# ConnectBox_Charger.net
KiCad netlist of a schematic drawn in EAGLE
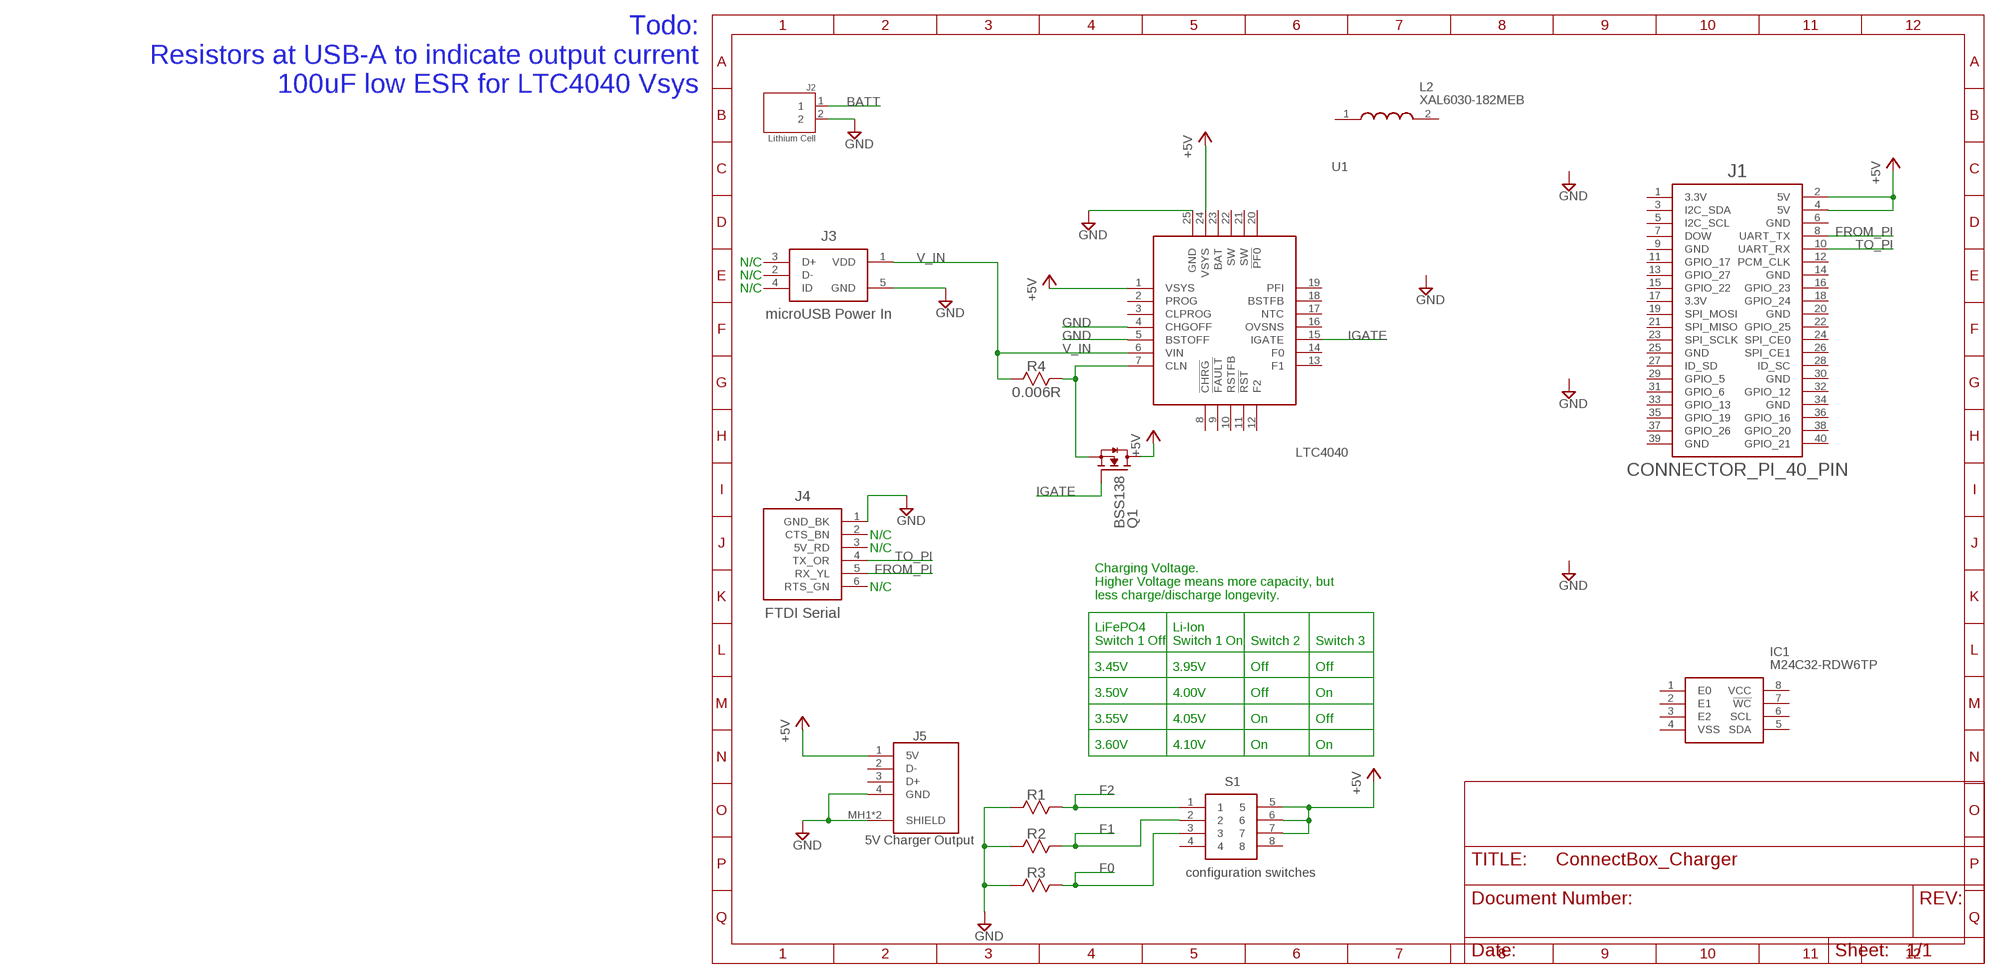
[diagram p0: schematic, sheet 1]

(export (version "E")
  (design (tool "Eeschema 10.0.6"))
  (components
    (comp (ref "IC1")
      (value "M24C32-RDW6TP")
      (footprint "eagle-import:SOP65P640X120-8N")
      (fields (field (name "MOUSER_PART_NUMBER") "511-M24C32-RDW6TP"))
      (libsource (lib "eagle-import") (part "M24C32-RDW6TP"))
    )
    (comp (ref "J1")
      (value "CONNECTOR_PI_40_PIN")
      (footprint "eagle-import:2X20")
      (libsource (lib "eagle-import") (part "CONNECTOR_PI_40_PIN"))
    )
    (comp (ref "J2")
      (value "Lithium Cell")
      (footprint "eagle-import:JST_S2B-PH-SM4-TB(LF)(SN)")
      (fields (field (name "MF") "JST Sales") (field (name "MP") "S2B-PH-SM4-TB_LF__SN_"))
      (libsource (lib "eagle-import") (part "S2B-PH-SM4-TB(LF)(SN)"))
    )
    (comp (ref "J3")
      (value "microUSB Power In")
      (footprint "eagle-import:FRAMATOME_10118194-0001LF")
      (fields (field (name "MF") "FCI") (field (name "MP") "10118194-0001LF"))
      (libsource (lib "eagle-import") (part "10118194-0001LF"))
    )
    (comp (ref "J4")
      (value "FTDI Serial")
      (footprint "eagle-import:ESQ-106-XX-X-S")
      (libsource (lib "eagle-import") (part "CONNECTOR-6-FTDI"))
    )
    (comp (ref "J5")
      (value "5V Charger Output")
      (footprint "eagle-import:SS52100001")
      (fields
        (field (name "MANUFACTURER_PART_NUMBER") "SS-52100-001")
        (field (name "MOUSER_PART_NUMBER") "530-SS-52100-001")
      )
      (libsource (lib "eagle-import") (part "SS-52100-001"))
    )
    (comp (ref "L2")
      (value "XAL6030-182MEB")
      (footprint "eagle-import:XAL6030182MEB")
      (fields (field (name "MOUSER_PART_NUMBER") "994-XAL6030-182MEB"))
      (libsource (lib "eagle-import") (part "XAL6030-182MEB"))
    )
    (comp (ref "Q1")
      (value "BSS138")
      (footprint "eagle-import:BSS138")
      (fields (field (name "MF") "Fairchild Semiconductor"))
      (libsource (lib "eagle-import") (part "BSS138"))
    )
    (comp (ref "R1")
      (value "RESISTOR0603")
      (footprint "eagle-import:RESC1608X55L25N")
      (libsource (lib "eagle-import") (part "RESISTOR0603"))
    )
    (comp (ref "R2")
      (value "RESISTOR0603")
      (footprint "eagle-import:RESC1608X55L25N")
      (libsource (lib "eagle-import") (part "RESISTOR0603"))
    )
    (comp (ref "R3")
      (value "RESISTOR0603")
      (footprint "eagle-import:RESC1608X55L25N")
      (libsource (lib "eagle-import") (part "RESISTOR0603"))
    )
    (comp (ref "R4")
      (value "0.006R")
      (footprint "eagle-import:RESC1608X55L25N")
      (libsource (lib "eagle-import") (part "RESISTOR0603"))
    )
    (comp (ref "S1")
      (value "configuration switches")
      (footprint "eagle-import:219-4LPST")
      (fields
        (field (name "MANUFACTURER_PART_NUMBER") "219-4LPST")
        (field (name "MOUSER_PART_NUMBER") "774-2194LPST")
        (field (name "RS_PART_NUMBER") "1774220")
      )
      (libsource (lib "eagle-import") (part "219-4LPST"))
    )
    (comp (ref "U1")
      (value "LTC4040")
      (footprint "eagle-import:QFN50P500X400X80-25N")
      (libsource (lib "eagle-import") (part "LTC4040"))
    )
  )
  (nets
    (net (code "1") (name "+5V") (class "Default")
      (node (ref "J1") (pin "2") (pinfunction "5V_2") (pintype "bidirectional"))
      (node (ref "J1") (pin "4") (pinfunction "5V_4") (pintype "bidirectional"))
      (node (ref "J5") (pin "1") (pinfunction "5V_1") (pintype "bidirectional"))
      (node (ref "Q1") (pin "D") (pinfunction "D_D") (pintype "passive"))
      (node (ref "S1") (pin "5") (pinfunction "5_5") (pintype "bidirectional"))
      (node (ref "S1") (pin "6") (pinfunction "6_6") (pintype "bidirectional"))
      (node (ref "S1") (pin "7") (pinfunction "7_7") (pintype "bidirectional"))
      (node (ref "U1") (pin "1") (pinfunction "VSYS_1") (pintype "bidirectional"))
      (node (ref "U1") (pin "24") (pinfunction "VSYS_24") (pintype "bidirectional"))
    )
    (net (code "2") (name "/BATT") (class "Default")
      (node (ref "J2") (pin "1") (pinfunction "1_1") (pintype "passive"))
    )
    (net (code "3") (name "/F0") (class "Default")
      (node (ref "R3") (pin "2") (pinfunction "2_2") (pintype "bidirectional"))
      (node (ref "S1") (pin "3") (pinfunction "3_3") (pintype "bidirectional"))
    )
    (net (code "4") (name "/F1") (class "Default")
      (node (ref "R2") (pin "2") (pinfunction "2_2") (pintype "bidirectional"))
      (node (ref "S1") (pin "2") (pinfunction "2_2") (pintype "bidirectional"))
    )
    (net (code "5") (name "/F2") (class "Default")
      (node (ref "R1") (pin "2") (pinfunction "2_2") (pintype "bidirectional"))
      (node (ref "S1") (pin "1") (pinfunction "1_1") (pintype "bidirectional"))
    )
    (net (code "6") (name "/FROM_PI") (class "Default")
      (node (ref "J1") (pin "8") (pinfunction "UART_TX_8") (pintype "bidirectional"))
      (node (ref "J4") (pin "5") (pinfunction "RX_YL_5") (pintype "bidirectional"))
    )
    (net (code "7") (name "/IGATE") (class "Default")
      (node (ref "Q1") (pin "G") (pinfunction "G_G") (pintype "passive"))
      (node (ref "U1") (pin "15") (pinfunction "IGATE_15") (pintype "bidirectional"))
    )
    (net (code "8") (name "/TO_PI") (class "Default")
      (node (ref "J1") (pin "10") (pinfunction "UART_RX_10") (pintype "bidirectional"))
      (node (ref "J4") (pin "4") (pinfunction "TX_OR_4") (pintype "bidirectional"))
    )
    (net (code "9") (name "/V_IN") (class "Default")
      (node (ref "J3") (pin "1") (pinfunction "VDD_1") (pintype "power_in"))
      (node (ref "R4") (pin "1") (pinfunction "1_1") (pintype "bidirectional"))
      (node (ref "U1") (pin "6") (pinfunction "VIN_6") (pintype "bidirectional"))
    )
    (net (code "10") (name "GND") (class "Default")
      (node (ref "J2") (pin "2") (pinfunction "2_2") (pintype "passive"))
      (node (ref "J3") (pin "5") (pinfunction "GND_5") (pintype "power_in"))
      (node (ref "J4") (pin "1") (pinfunction "GND_BK_1") (pintype "bidirectional"))
      (node (ref "J5") (pin "4") (pinfunction "GND_4") (pintype "bidirectional"))
      (node (ref "J5") (pin "MH1") (pinfunction "SHIELD_MH1") (pintype "bidirectional"))
      (node (ref "J5") (pin "MH2") (pinfunction "SHIELD_MH2") (pintype "bidirectional"))
      (node (ref "R1") (pin "1") (pinfunction "1_1") (pintype "bidirectional"))
      (node (ref "R2") (pin "1") (pinfunction "1_1") (pintype "bidirectional"))
      (node (ref "R3") (pin "1") (pinfunction "1_1") (pintype "bidirectional"))
      (node (ref "U1") (pin "25") (pinfunction "GND_25") (pintype "bidirectional"))
      (node (ref "U1") (pin "4") (pinfunction "CHGOFF_4") (pintype "bidirectional"))
      (node (ref "U1") (pin "5") (pinfunction "BSTOFF_5") (pintype "bidirectional"))
    )
    (net (code "11") (name "Net-(U1-CLN)") (class "Default")
      (node (ref "Q1") (pin "S") (pinfunction "S_S") (pintype "passive"))
      (node (ref "R4") (pin "2") (pinfunction "2_2") (pintype "bidirectional"))
      (node (ref "U1") (pin "7") (pinfunction "CLN_7") (pintype "bidirectional"))
    )
    (net (code "12") (name "unconnected-(IC1-E0-Pad1)") (class "Default")
      (node (ref "IC1") (pin "1") (pinfunction "E0_1") (pintype "bidirectional"))
    )
    (net (code "13") (name "unconnected-(IC1-E1-Pad2)") (class "Default")
      (node (ref "IC1") (pin "2") (pinfunction "E1_2") (pintype "bidirectional"))
    )
    (net (code "14") (name "unconnected-(IC1-E2-Pad3)") (class "Default")
      (node (ref "IC1") (pin "3") (pinfunction "E2_3") (pintype "bidirectional"))
    )
    (net (code "15") (name "unconnected-(IC1-SCL-Pad6)") (class "Default")
      (node (ref "IC1") (pin "6") (pinfunction "SCL_6") (pintype "bidirectional"))
    )
    (net (code "16") (name "unconnected-(IC1-SDA-Pad5)") (class "Default")
      (node (ref "IC1") (pin "5") (pinfunction "SDA_5") (pintype "bidirectional"))
    )
    (net (code "17") (name "unconnected-(IC1-VCC-Pad8)") (class "Default")
      (node (ref "IC1") (pin "8") (pinfunction "VCC_8") (pintype "bidirectional"))
    )
    (net (code "18") (name "unconnected-(IC1-VSS-Pad4)") (class "Default")
      (node (ref "IC1") (pin "4") (pinfunction "VSS_4") (pintype "bidirectional"))
    )
    (net (code "19") (name "unconnected-(IC1-~{WC}-Pad7)") (class "Default")
      (node (ref "IC1") (pin "7") (pinfunction "~{WC}_7") (pintype "bidirectional"))
    )
    (net (code "20") (name "unconnected-(J1-3.3V-Pad1)") (class "Default")
      (node (ref "J1") (pin "1") (pinfunction "3.3V_1") (pintype "bidirectional"))
    )
    (net (code "21") (name "unconnected-(J1-3.3V-Pad17)") (class "Default")
      (node (ref "J1") (pin "17") (pinfunction "3.3V_17") (pintype "bidirectional"))
    )
    (net (code "22") (name "unconnected-(J1-DOW-Pad7)") (class "Default")
      (node (ref "J1") (pin "7") (pinfunction "DOW_7") (pintype "bidirectional"))
    )
    (net (code "23") (name "unconnected-(J1-GND-Pad6)") (class "Default")
      (node (ref "J1") (pin "6") (pinfunction "GND_6") (pintype "bidirectional"))
    )
    (net (code "24") (name "unconnected-(J1-GND-Pad9)") (class "Default")
      (node (ref "J1") (pin "9") (pinfunction "GND_9") (pintype "bidirectional"))
    )
    (net (code "25") (name "unconnected-(J1-GND-Pad14)") (class "Default")
      (node (ref "J1") (pin "14") (pinfunction "GND_14") (pintype "bidirectional"))
    )
    (net (code "26") (name "unconnected-(J1-GND-Pad20)") (class "Default")
      (node (ref "J1") (pin "20") (pinfunction "GND_20") (pintype "bidirectional"))
    )
    (net (code "27") (name "unconnected-(J1-GND-Pad25)") (class "Default")
      (node (ref "J1") (pin "25") (pinfunction "GND_25") (pintype "bidirectional"))
    )
    (net (code "28") (name "unconnected-(J1-GND-Pad30)") (class "Default")
      (node (ref "J1") (pin "30") (pinfunction "GND_30") (pintype "bidirectional"))
    )
    (net (code "29") (name "unconnected-(J1-GND-Pad34)") (class "Default")
      (node (ref "J1") (pin "34") (pinfunction "GND_34") (pintype "bidirectional"))
    )
    (net (code "30") (name "unconnected-(J1-GND-Pad39)") (class "Default")
      (node (ref "J1") (pin "39") (pinfunction "GND_39") (pintype "bidirectional"))
    )
    (net (code "31") (name "unconnected-(J1-GPIO_5-Pad29)") (class "Default")
      (node (ref "J1") (pin "29") (pinfunction "GPIO_5_29") (pintype "bidirectional"))
    )
    (net (code "32") (name "unconnected-(J1-GPIO_6-Pad31)") (class "Default")
      (node (ref "J1") (pin "31") (pinfunction "GPIO_6_31") (pintype "bidirectional"))
    )
    (net (code "33") (name "unconnected-(J1-GPIO_12-Pad32)") (class "Default")
      (node (ref "J1") (pin "32") (pinfunction "GPIO_12_32") (pintype "bidirectional"))
    )
    (net (code "34") (name "unconnected-(J1-GPIO_13-Pad33)") (class "Default")
      (node (ref "J1") (pin "33") (pinfunction "GPIO_13_33") (pintype "bidirectional"))
    )
    (net (code "35") (name "unconnected-(J1-GPIO_16-Pad36)") (class "Default")
      (node (ref "J1") (pin "36") (pinfunction "GPIO_16_36") (pintype "bidirectional"))
    )
    (net (code "36") (name "unconnected-(J1-GPIO_17-Pad11)") (class "Default")
      (node (ref "J1") (pin "11") (pinfunction "GPIO_17_11") (pintype "bidirectional"))
    )
    (net (code "37") (name "unconnected-(J1-GPIO_19-Pad35)") (class "Default")
      (node (ref "J1") (pin "35") (pinfunction "GPIO_19_35") (pintype "bidirectional"))
    )
    (net (code "38") (name "unconnected-(J1-GPIO_20-Pad38)") (class "Default")
      (node (ref "J1") (pin "38") (pinfunction "GPIO_20_38") (pintype "bidirectional"))
    )
    (net (code "39") (name "unconnected-(J1-GPIO_21-Pad40)") (class "Default")
      (node (ref "J1") (pin "40") (pinfunction "GPIO_21_40") (pintype "bidirectional"))
    )
    (net (code "40") (name "unconnected-(J1-GPIO_22-Pad15)") (class "Default")
      (node (ref "J1") (pin "15") (pinfunction "GPIO_22_15") (pintype "bidirectional"))
    )
    (net (code "41") (name "unconnected-(J1-GPIO_23-Pad16)") (class "Default")
      (node (ref "J1") (pin "16") (pinfunction "GPIO_23_16") (pintype "bidirectional"))
    )
    (net (code "42") (name "unconnected-(J1-GPIO_24-Pad18)") (class "Default")
      (node (ref "J1") (pin "18") (pinfunction "GPIO_24_18") (pintype "bidirectional"))
    )
    (net (code "43") (name "unconnected-(J1-GPIO_25-Pad22)") (class "Default")
      (node (ref "J1") (pin "22") (pinfunction "GPIO_25_22") (pintype "bidirectional"))
    )
    (net (code "44") (name "unconnected-(J1-GPIO_26-Pad37)") (class "Default")
      (node (ref "J1") (pin "37") (pinfunction "GPIO_26_37") (pintype "bidirectional"))
    )
    (net (code "45") (name "unconnected-(J1-GPIO_27-Pad13)") (class "Default")
      (node (ref "J1") (pin "13") (pinfunction "GPIO_27_13") (pintype "bidirectional"))
    )
    (net (code "46") (name "unconnected-(J1-I2C_SCL-Pad5)") (class "Default")
      (node (ref "J1") (pin "5") (pinfunction "I2C_SCL_5") (pintype "bidirectional"))
    )
    (net (code "47") (name "unconnected-(J1-I2C_SDA-Pad3)") (class "Default")
      (node (ref "J1") (pin "3") (pinfunction "I2C_SDA_3") (pintype "bidirectional"))
    )
    (net (code "48") (name "unconnected-(J1-ID_SC-Pad28)") (class "Default")
      (node (ref "J1") (pin "28") (pinfunction "ID_SC_28") (pintype "bidirectional"))
    )
    (net (code "49") (name "unconnected-(J1-ID_SD-Pad27)") (class "Default")
      (node (ref "J1") (pin "27") (pinfunction "ID_SD_27") (pintype "bidirectional"))
    )
    (net (code "50") (name "unconnected-(J1-PCM_CLK-Pad12)") (class "Default")
      (node (ref "J1") (pin "12") (pinfunction "PCM_CLK_12") (pintype "bidirectional"))
    )
    (net (code "51") (name "unconnected-(J1-SPI_CE0-Pad24)") (class "Default")
      (node (ref "J1") (pin "24") (pinfunction "SPI_CE0_24") (pintype "bidirectional"))
    )
    (net (code "52") (name "unconnected-(J1-SPI_CE1-Pad26)") (class "Default")
      (node (ref "J1") (pin "26") (pinfunction "SPI_CE1_26") (pintype "bidirectional"))
    )
    (net (code "53") (name "unconnected-(J1-SPI_MISO-Pad21)") (class "Default")
      (node (ref "J1") (pin "21") (pinfunction "SPI_MISO_21") (pintype "bidirectional"))
    )
    (net (code "54") (name "unconnected-(J1-SPI_MOSI-Pad19)") (class "Default")
      (node (ref "J1") (pin "19") (pinfunction "SPI_MOSI_19") (pintype "bidirectional"))
    )
    (net (code "55") (name "unconnected-(J1-SPI_SCLK-Pad23)") (class "Default")
      (node (ref "J1") (pin "23") (pinfunction "SPI_SCLK_23") (pintype "bidirectional"))
    )
    (net (code "56") (name "unconnected-(J3-D+-Pad3)") (class "Default")
      (node (ref "J3") (pin "3") (pinfunction "D+_3") (pintype "bidirectional"))
    )
    (net (code "57") (name "unconnected-(J3-D--Pad2)") (class "Default")
      (node (ref "J3") (pin "2") (pinfunction "D-_2") (pintype "bidirectional"))
    )
    (net (code "58") (name "unconnected-(J3-ID-Pad4)") (class "Default")
      (node (ref "J3") (pin "4") (pinfunction "ID_4") (pintype "passive"))
    )
    (net (code "59") (name "unconnected-(J4-5V_RD-Pad3)") (class "Default")
      (node (ref "J4") (pin "3") (pinfunction "5V_RD_3") (pintype "bidirectional"))
    )
    (net (code "60") (name "unconnected-(J4-CTS_BN-Pad2)") (class "Default")
      (node (ref "J4") (pin "2") (pinfunction "CTS_BN_2") (pintype "bidirectional"))
    )
    (net (code "61") (name "unconnected-(J4-RTS_GN-Pad6)") (class "Default")
      (node (ref "J4") (pin "6") (pinfunction "RTS_GN_6") (pintype "bidirectional"))
    )
    (net (code "62") (name "unconnected-(J5-D+-Pad3)") (class "Default")
      (node (ref "J5") (pin "3") (pinfunction "D+_3") (pintype "bidirectional"))
    )
    (net (code "63") (name "unconnected-(J5-D--Pad2)") (class "Default")
      (node (ref "J5") (pin "2") (pinfunction "D-_2") (pintype "bidirectional"))
    )
    (net (code "64") (name "unconnected-(L2-Pad1)") (class "Default")
      (node (ref "L2") (pin "1") (pinfunction "1_1") (pintype "bidirectional"))
    )
    (net (code "65") (name "unconnected-(L2-Pad2)") (class "Default")
      (node (ref "L2") (pin "2") (pinfunction "2_2") (pintype "bidirectional"))
    )
    (net (code "66") (name "unconnected-(S1-Pad4)") (class "Default")
      (node (ref "S1") (pin "4") (pinfunction "4_4") (pintype "bidirectional"))
    )
    (net (code "67") (name "unconnected-(S1-Pad8)") (class "Default")
      (node (ref "S1") (pin "8") (pinfunction "8_8") (pintype "bidirectional"))
    )
    (net (code "68") (name "unconnected-(U1-BAT-Pad23)") (class "Default")
      (node (ref "U1") (pin "23") (pinfunction "BAT_23") (pintype "bidirectional"))
    )
    (net (code "69") (name "unconnected-(U1-BSTFB-Pad18)") (class "Default")
      (node (ref "U1") (pin "18") (pinfunction "BSTFB_18") (pintype "bidirectional"))
    )
    (net (code "70") (name "unconnected-(U1-CLPROG-Pad3)") (class "Default")
      (node (ref "U1") (pin "3") (pinfunction "CLPROG_3") (pintype "bidirectional"))
    )
    (net (code "71") (name "unconnected-(U1-F0-Pad14)") (class "Default")
      (node (ref "U1") (pin "14") (pinfunction "F0_14") (pintype "bidirectional"))
    )
    (net (code "72") (name "unconnected-(U1-F1-Pad13)") (class "Default")
      (node (ref "U1") (pin "13") (pinfunction "F1_13") (pintype "bidirectional"))
    )
    (net (code "73") (name "unconnected-(U1-F2-Pad12)") (class "Default")
      (node (ref "U1") (pin "12") (pinfunction "F2_12") (pintype "bidirectional"))
    )
    (net (code "74") (name "unconnected-(U1-NTC-Pad17)") (class "Default")
      (node (ref "U1") (pin "17") (pinfunction "NTC_17") (pintype "bidirectional"))
    )
    (net (code "75") (name "unconnected-(U1-OVSNS-Pad16)") (class "Default")
      (node (ref "U1") (pin "16") (pinfunction "OVSNS_16") (pintype "bidirectional"))
    )
    (net (code "76") (name "unconnected-(U1-PFI-Pad19)") (class "Default")
      (node (ref "U1") (pin "19") (pinfunction "PFI_19") (pintype "bidirectional"))
    )
    (net (code "77") (name "unconnected-(U1-PROG-Pad2)") (class "Default")
      (node (ref "U1") (pin "2") (pinfunction "PROG_2") (pintype "bidirectional"))
    )
    (net (code "78") (name "unconnected-(U1-RSTFB-Pad10)") (class "Default")
      (node (ref "U1") (pin "10") (pinfunction "RSTFB_10") (pintype "bidirectional"))
    )
    (net (code "79") (name "unconnected-(U1-SW-Pad21)") (class "Default")
      (node (ref "U1") (pin "21") (pinfunction "SW_21") (pintype "bidirectional"))
    )
    (net (code "80") (name "unconnected-(U1-SW-Pad22)") (class "Default")
      (node (ref "U1") (pin "22") (pinfunction "SW_22") (pintype "bidirectional"))
    )
    (net (code "81") (name "unconnected-(U1-~{CHRG}-Pad8)") (class "Default")
      (node (ref "U1") (pin "8") (pinfunction "~{CHRG}_8") (pintype "bidirectional"))
    )
    (net (code "82") (name "unconnected-(U1-~{FAULT}-Pad9)") (class "Default")
      (node (ref "U1") (pin "9") (pinfunction "~{FAULT}_9") (pintype "bidirectional"))
    )
    (net (code "83") (name "unconnected-(U1-~{PF0}-Pad20)") (class "Default")
      (node (ref "U1") (pin "20") (pinfunction "~{PF0}_20") (pintype "bidirectional"))
    )
    (net (code "84") (name "unconnected-(U1-~{RST}-Pad11)") (class "Default")
      (node (ref "U1") (pin "11") (pinfunction "~{RST}_11") (pintype "bidirectional"))
    )
  )
)
